# atmega.net
KiCad netlist of a schematic drawn in Altium Designer
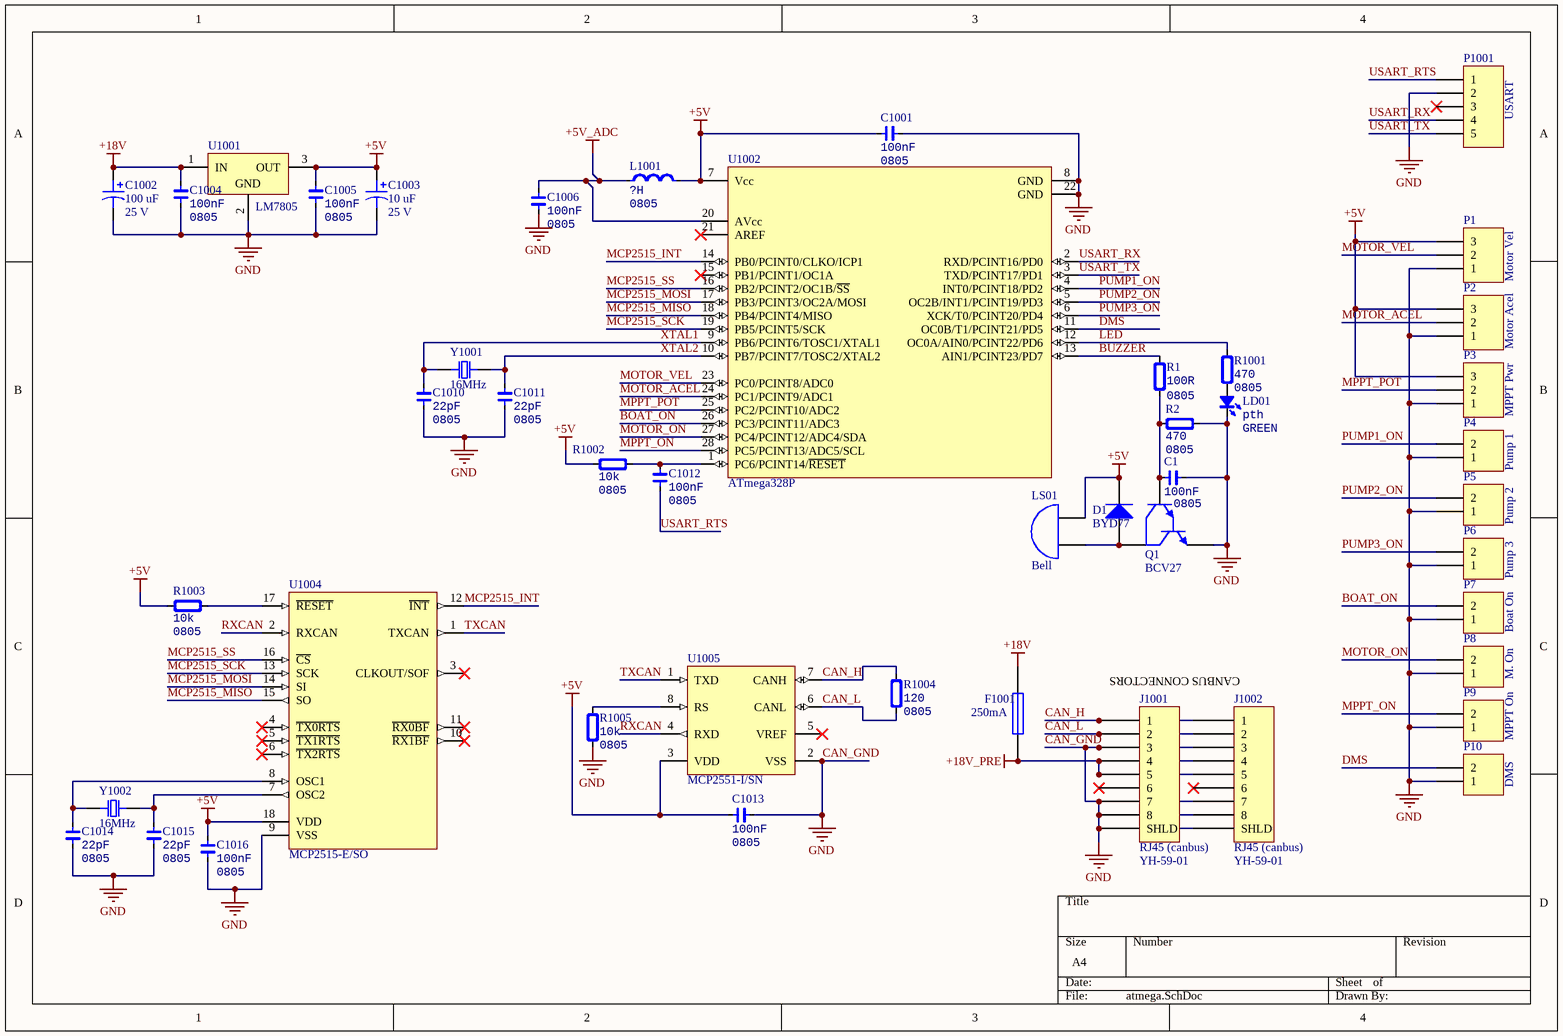
[diagram p0: atmega.SchDoc]

(export (version "E")
  (design (tool "Eeschema 10.0.6"))
  (components
    (comp (ref "C1")
      (value "100nF")
      (footprint "Zenite_Footprints:0805C")
      (description "Capacitor")
      (fields (field (name "TYPE") "0805"))
      (libsource (lib "") (part "Cap_0805_2"))
    )
    (comp (ref "C1001")
      (value "100nF")
      (footprint "Zenite_Footprints:0805C")
      (description "Capacitor")
      (fields (field (name "TYPE") "0805"))
      (libsource (lib "") (part "Cap_0805_2"))
    )
    (comp (ref "C1002")
      (value "100 uF")
      (footprint "CP3.5mm-8.0mm")
      (description "Solid Aluminum Capacitor with Organic Semiconductor Electrolyte: 100uF, 10V, Bulk Pack")
      (fields (field (name "VOLTAGE") "25 V") (field (name "Comment") "CapacitorPol"))
      (libsource (lib "R2R - Nova") (part "CapacitorPol"))
    )
    (comp (ref "C1003")
      (value "10 uF")
      (footprint "CP3.5mm-8.0mm")
      (description "Solid Aluminum Capacitor with Organic Semiconductor Electrolyte: 100uF, 10V, Bulk Pack")
      (fields (field (name "VOLTAGE") "25 V") (field (name "Comment") "CapacitorPol"))
      (libsource (lib "R2R - Nova") (part "CapacitorPol"))
    )
    (comp (ref "C1004")
      (value "100nF")
      (footprint "Zenite_Footprints:0805C")
      (description "Capacitor")
      (fields (field (name "TYPE") "0805"))
      (libsource (lib "SCH_Passive") (part "Cap_0805"))
    )
    (comp (ref "C1005")
      (value "100nF")
      (footprint "Zenite_Footprints:0805C")
      (description "Capacitor")
      (fields (field (name "TYPE") "0805"))
      (libsource (lib "SCH_Passive") (part "Cap_0805"))
    )
    (comp (ref "C1006")
      (value "100nF")
      (footprint "Zenite_Footprints:0805C")
      (description "Capacitor")
      (fields (field (name "TYPE") "0805"))
      (libsource (lib "SCH_Passive") (part "Cap_0805"))
    )
    (comp (ref "C1010")
      (value "22pF")
      (footprint "Zenite_Footprints:0805C")
      (description "Capacitor")
      (fields (field (name "TYPE") "0805"))
      (libsource (lib "SCH_Passive") (part "Cap_0805"))
    )
    (comp (ref "C1011")
      (value "22pF")
      (footprint "Zenite_Footprints:0805C")
      (description "Capacitor")
      (fields (field (name "TYPE") "0805"))
      (libsource (lib "SCH_Passive") (part "Cap_0805"))
    )
    (comp (ref "C1012")
      (value "100nF")
      (footprint "Zenite_Footprints:0805C")
      (description "Capacitor")
      (fields (field (name "TYPE") "0805"))
      (libsource (lib "") (part "Cap_0805_1"))
    )
    (comp (ref "C1013")
      (value "100nF")
      (footprint "Zenite_Footprints:0805C")
      (description "Capacitor")
      (fields (field (name "TYPE") "0805"))
      (libsource (lib "") (part "Cap_0805_2"))
    )
    (comp (ref "C1014")
      (value "22pF")
      (footprint "Zenite_Footprints:0805C")
      (description "Capacitor")
      (fields (field (name "TYPE") "0805"))
      (libsource (lib "SCH_Passive") (part "Cap_0805"))
    )
    (comp (ref "C1015")
      (value "22pF")
      (footprint "Zenite_Footprints:0805C")
      (description "Capacitor")
      (fields (field (name "TYPE") "0805"))
      (libsource (lib "SCH_Passive") (part "Cap_0805"))
    )
    (comp (ref "C1016")
      (value "100nF")
      (footprint "Zenite_Footprints:0805C")
      (description "Capacitor")
      (fields (field (name "TYPE") "0805"))
      (libsource (lib "") (part "Cap_0805_1"))
    )
    (comp (ref "D1")
      (value "BYD77")
      (footprint "DSO-C2/X2.3")
      (description "Default Diode")
      (libsource (lib "Miscellaneous Devices") (part "Diode"))
    )
    (comp (ref "F1001")
      (value "250mA")
      (footprint "Porta Fusivel")
      (description "Fuse")
      (libsource (lib "Miscellaneous Devices") (part "Fuse 1"))
    )
    (comp (ref "J1001")
      (value "RJ45 (canbus)")
      (footprint "ASSMANN A-2004-2-4-LP/FS")
      (description "YH-59-01")
      (fields (field (name "ALTIUM_VALUE") "YH-59-01"))
      (libsource (lib "Connectors") (part "Modular Jack with Shield"))
    )
    (comp (ref "J1002")
      (value "RJ45 (canbus)")
      (footprint "ASSMANN A-2004-2-4-LP/FS")
      (description "YH-59-01")
      (fields (field (name "ALTIUM_VALUE") "YH-59-01"))
      (libsource (lib "Connectors") (part "Modular Jack with Shield"))
    )
    (comp (ref "L1001")
      (value "?H")
      (footprint "Zenite_Footprints:0805L")
      (description "Inductor")
      (fields (field (name "TYPE") "0805"))
      (libsource (lib "SCH_Passive") (part "Ind_0805"))
    )
    (comp (ref "LD01")
      (value "GREEN")
      (footprint "LED3MM")
      (description "LED")
      (fields (field (name "TYPE") "pth"))
      (libsource (lib "SCH_Active") (part "LED_0805"))
    )
    (comp (ref "LS01")
      (value "Bell")
      (footprint "Buzzer5V")
      (description "Electrical Bell")
      (libsource (lib "Miscellaneous Devices") (part "Bell"))
    )
    (comp (ref "P1")
      (value "Motor Vel")
      (footprint "KRE_3")
      (description "Header, 3-Pin")
      (libsource (lib "Miscellaneous Connectors") (part "Header 3"))
    )
    (comp (ref "P2")
      (value "Motor Acel")
      (footprint "KRE_3")
      (description "Header, 3-Pin")
      (libsource (lib "Miscellaneous Connectors") (part "Header 3"))
    )
    (comp (ref "P3")
      (value "MPPT Pwr")
      (footprint "KRE_3")
      (description "Header, 3-Pin")
      (libsource (lib "Miscellaneous Connectors") (part "Header 3"))
    )
    (comp (ref "P4")
      (value "Pump 1")
      (footprint "KRE_2")
      (description "Terminal Block 1x2")
      (libsource (lib "R2R - Nova") (part "KRE_2"))
    )
    (comp (ref "P5")
      (value "Pump 2")
      (footprint "KRE_2")
      (description "Terminal Block 1x2")
      (libsource (lib "R2R - Nova") (part "KRE_2"))
    )
    (comp (ref "P6")
      (value "Pump 3")
      (footprint "KRE_2")
      (description "Terminal Block 1x2")
      (libsource (lib "R2R - Nova") (part "KRE_2"))
    )
    (comp (ref "P7")
      (value "Boat On")
      (footprint "KRE_2")
      (description "Terminal Block 1x2")
      (libsource (lib "R2R - Nova") (part "KRE_2"))
    )
    (comp (ref "P8")
      (value "M. On")
      (footprint "KRE_2")
      (description "Terminal Block 1x2")
      (libsource (lib "R2R - Nova") (part "KRE_2"))
    )
    (comp (ref "P9")
      (value "MPPT On")
      (footprint "KRE_2")
      (description "Terminal Block 1x2")
      (libsource (lib "R2R - Nova") (part "KRE_2"))
    )
    (comp (ref "P10")
      (value "DMS")
      (footprint "KRE_2")
      (description "Terminal Block 1x2")
      (libsource (lib "R2R - Nova") (part "KRE_2"))
    )
    (comp (ref "P1001")
      (value "USART")
      (footprint "Zenite_Footprints:HDR1X5")
      (description "Header, 5-Pin")
      (libsource (lib "R2R - Nova") (part "Header 5"))
    )
    (comp (ref "Q1")
      (value "BCV27")
      (footprint "SOT95P240-3N")
      (description "NPN Darlington Bipolar Transistor")
      (libsource (lib "Miscellaneous Devices") (part "NPN1"))
    )
    (comp (ref "R1")
      (value "100R")
      (footprint "Zenite_Footprints:0805R")
      (description "Resistor")
      (fields (field (name "TYPE") "0805"))
      (libsource (lib "SCH_Passive") (part "Res_0805"))
    )
    (comp (ref "R2")
      (value "470")
      (footprint "Zenite_Footprints:0805R")
      (description "Resistor")
      (fields (field (name "TYPE") "0805"))
      (libsource (lib "SCH_Passive") (part "Res_0805"))
    )
    (comp (ref "R1001")
      (value "470")
      (footprint "Zenite_Footprints:0805R")
      (description "Resistor")
      (fields (field (name "TYPE") "0805"))
      (libsource (lib "SCH_Passive") (part "Res_0805"))
    )
    (comp (ref "R1002")
      (value "10k")
      (footprint "Zenite_Footprints:0805R")
      (description "Resistor")
      (fields (field (name "TYPE") "0805"))
      (libsource (lib "SCH_Passive") (part "Res_0805"))
    )
    (comp (ref "R1003")
      (value "10k")
      (footprint "Zenite_Footprints:0805R")
      (description "Resistor")
      (fields (field (name "TYPE") "0805"))
      (libsource (lib "SCH_Passive") (part "Res_0805"))
    )
    (comp (ref "R1004")
      (value "120")
      (footprint "Zenite_Footprints:0805R")
      (description "Resistor")
      (fields (field (name "TYPE") "0805"))
      (libsource (lib "SCH_Passive") (part "Res_0805"))
    )
    (comp (ref "R1005")
      (value "10k")
      (footprint "Zenite_Footprints:0805R")
      (description "Resistor")
      (fields (field (name "TYPE") "0805"))
      (libsource (lib "SCH_Passive") (part "Res_0805"))
    )
    (comp (ref "U1001")
      (value "LM7805")
      (footprint "TO220_deitado")
      (description "Positive-Voltage Regulator")
      (libsource (lib "TI Power Mgt Voltage Regulator") (part "µA7805CKC"))
    )
    (comp (ref "U1002")
      (value "ATmega328P")
      (footprint "DIP28-300(100)")
      (libsource (lib "R2R - Nova") (part "ATmega328P"))
    )
    (comp (ref "U1004")
      (value "MCP2515-E/SO")
      (footprint "WSO18_L")
      (description "Stand-Alone CAN Controller With SPI Interface, 18-Pin SOIC, Extended Temperature")
      (libsource (lib "Altium Content Vault") (part "COM-CAN-MCP2515-18"))
    )
    (comp (ref "U1005")
      (value "MCP2551-I/SN")
      (footprint "SOIC08-150(50)")
      (libsource (lib "Altium Content Vault") (part "MCHP-MCP2551-SN8"))
    )
    (comp (ref "Y1001")
      (value "16MHz")
      (footprint "HC49-US-THT")
      (description "Crystal")
      (libsource (lib "R2R - Nova") (part "Crystal"))
    )
    (comp (ref "Y1002")
      (value "16MHz")
      (footprint "HC49-US-THT")
      (description "Crystal")
      (libsource (lib "R2R - Nova") (part "Crystal"))
    )
  )
  (nets
    (net (code "1") (name "+5V") (class "Default")
      (node (ref "C1001") (pin "1") (pinfunction "1_1") (pintype "passive"))
      (node (ref "C1003") (pin "1") (pinfunction "1_1") (pintype "passive"))
      (node (ref "C1005") (pin "2") (pinfunction "2_2") (pintype "passive"))
      (node (ref "C1013") (pin "1") (pinfunction "1_1") (pintype "passive"))
      (node (ref "C1016") (pin "1") (pinfunction "1_1") (pintype "passive"))
      (node (ref "D1") (pin "2") (pinfunction "K_2") (pintype "passive"))
      (node (ref "L1001") (pin "2") (pinfunction "2_2") (pintype "passive"))
      (node (ref "LS01") (pin "2") (pinfunction "B_2") (pintype "passive"))
      (node (ref "P1") (pin "3") (pinfunction "3_3") (pintype "passive"))
      (node (ref "P2") (pin "3") (pinfunction "3_3") (pintype "passive"))
      (node (ref "P3") (pin "3") (pinfunction "3_3") (pintype "passive"))
      (node (ref "R1002") (pin "1") (pinfunction "1_1") (pintype "passive"))
      (node (ref "R1003") (pin "1") (pinfunction "1_1") (pintype "passive"))
      (node (ref "U1001") (pin "3") (pinfunction "OUT_3") (pintype "power_in"))
      (node (ref "U1002") (pin "7") (pinfunction "Vcc_7") (pintype "passive"))
      (node (ref "U1004") (pin "18") (pinfunction "VDD_18") (pintype "power_in"))
      (node (ref "U1005") (pin "3") (pinfunction "VDD_3") (pintype "power_in"))
    )
    (net (code "2") (name "+5V_ADC") (class "Default")
      (node (ref "C1006") (pin "2") (pinfunction "2_2") (pintype "passive"))
      (node (ref "L1001") (pin "1") (pinfunction "1_1") (pintype "passive"))
      (node (ref "U1002") (pin "20") (pinfunction "AVcc_20") (pintype "passive"))
    )
    (net (code "3") (name "+18V") (class "Default")
      (node (ref "C1002") (pin "1") (pinfunction "1_1") (pintype "passive"))
      (node (ref "C1004") (pin "2") (pinfunction "2_2") (pintype "passive"))
      (node (ref "F1001") (pin "1") (pinfunction "1_1") (pintype "passive"))
      (node (ref "U1001") (pin "1") (pinfunction "IN_1") (pintype "power_in"))
    )
    (net (code "4") (name "+18V_PRE") (class "Default")
      (node (ref "F1001") (pin "2") (pinfunction "2_2") (pintype "passive"))
      (node (ref "J1001") (pin "4") (pinfunction "4_4") (pintype "passive"))
      (node (ref "J1001") (pin "5") (pinfunction "5_5") (pintype "passive"))
      (node (ref "J1002") (pin "4") (pinfunction "4_4") (pintype "passive"))
      (node (ref "J1002") (pin "5") (pinfunction "5_5") (pintype "passive"))
    )
    (net (code "5") (name "/BOAT_ON") (class "Default")
      (node (ref "P7") (pin "2") (pinfunction "2_2") (pintype "passive"))
      (node (ref "U1002") (pin "26") (pinfunction "PC3/PCINT11/ADC3_26") (pintype "bidirectional"))
    )
    (net (code "6") (name "/BUZZER") (class "Default")
      (node (ref "R1") (pin "1") (pinfunction "1_1") (pintype "passive"))
      (node (ref "U1002") (pin "13") (pinfunction "AIN1/PCINT23/PD7_13") (pintype "bidirectional"))
    )
    (net (code "7") (name "/CAN_H") (class "Default")
      (node (ref "J1001") (pin "1") (pinfunction "1_1") (pintype "passive"))
      (node (ref "J1002") (pin "1") (pinfunction "1_1") (pintype "passive"))
      (node (ref "R1004") (pin "2") (pinfunction "2_2") (pintype "passive"))
      (node (ref "U1005") (pin "7") (pinfunction "CANH_7") (pintype "bidirectional"))
    )
    (net (code "8") (name "/CAN_L") (class "Default")
      (node (ref "J1001") (pin "2") (pinfunction "2_2") (pintype "passive"))
      (node (ref "J1002") (pin "2") (pinfunction "2_2") (pintype "passive"))
      (node (ref "R1004") (pin "1") (pinfunction "1_1") (pintype "passive"))
      (node (ref "U1005") (pin "6") (pinfunction "CANL_6") (pintype "bidirectional"))
    )
    (net (code "9") (name "/DMS") (class "Default")
      (node (ref "P10") (pin "2") (pinfunction "2_2") (pintype "passive"))
      (node (ref "U1002") (pin "11") (pinfunction "OC0B/T1/PCINT21/PD5_11") (pintype "bidirectional"))
    )
    (net (code "10") (name "/LED") (class "Default")
      (node (ref "R1001") (pin "2") (pinfunction "2_2") (pintype "passive"))
      (node (ref "U1002") (pin "12") (pinfunction "OC0A/AIN0/PCINT22/PD6_12") (pintype "bidirectional"))
    )
    (net (code "11") (name "/MCP2515_INT") (class "Default")
      (node (ref "U1002") (pin "14") (pinfunction "PB0/PCINT0/CLKO/ICP1_14") (pintype "bidirectional"))
      (node (ref "U1004") (pin "12") (pinfunction "~{INT}_12") (pintype "output"))
    )
    (net (code "12") (name "/MCP2515_MISO") (class "Default")
      (node (ref "U1002") (pin "18") (pinfunction "PB4/PCINT4/MISO_18") (pintype "bidirectional"))
      (node (ref "U1004") (pin "15") (pinfunction "SO_15") (pintype "output"))
    )
    (net (code "13") (name "/MCP2515_MOSI") (class "Default")
      (node (ref "U1002") (pin "17") (pinfunction "PB3/PCINT3/OC2A/MOSI_17") (pintype "bidirectional"))
      (node (ref "U1004") (pin "14") (pinfunction "SI_14") (pintype "input"))
    )
    (net (code "14") (name "/MCP2515_SCK") (class "Default")
      (node (ref "U1002") (pin "19") (pinfunction "PB5/PCINT5/SCK_19") (pintype "bidirectional"))
      (node (ref "U1004") (pin "13") (pinfunction "SCK_13") (pintype "input"))
    )
    (net (code "15") (name "/MCP2515_SS") (class "Default")
      (node (ref "U1002") (pin "16") (pinfunction "PB2/PCINT2/OC1B/~{SS}_16") (pintype "bidirectional"))
      (node (ref "U1004") (pin "16") (pinfunction "~{CS}_16") (pintype "input"))
    )
    (net (code "16") (name "/MOTOR_ACEL") (class "Default")
      (node (ref "P2") (pin "2") (pinfunction "2_2") (pintype "passive"))
      (node (ref "U1002") (pin "24") (pinfunction "PC1/PCINT9/ADC1_24") (pintype "bidirectional"))
    )
    (net (code "17") (name "/MOTOR_ON") (class "Default")
      (node (ref "P8") (pin "2") (pinfunction "2_2") (pintype "passive"))
      (node (ref "U1002") (pin "27") (pinfunction "PC4/PCINT12/ADC4/SDA_27") (pintype "bidirectional"))
    )
    (net (code "18") (name "/MOTOR_VEL") (class "Default")
      (node (ref "P1") (pin "2") (pinfunction "2_2") (pintype "passive"))
      (node (ref "U1002") (pin "23") (pinfunction "PC0/PCINT8/ADC0_23") (pintype "bidirectional"))
    )
    (net (code "19") (name "/MPPT_ON") (class "Default")
      (node (ref "P9") (pin "2") (pinfunction "2_2") (pintype "passive"))
      (node (ref "U1002") (pin "28") (pinfunction "PC5/PCINT13/ADC5/SCL_28") (pintype "bidirectional"))
    )
    (net (code "20") (name "/MPPT_POT") (class "Default")
      (node (ref "P3") (pin "2") (pinfunction "2_2") (pintype "passive"))
      (node (ref "U1002") (pin "25") (pinfunction "PC2/PCINT10/ADC2_25") (pintype "bidirectional"))
    )
    (net (code "21") (name "/PUMP1_ON") (class "Default")
      (node (ref "P4") (pin "2") (pinfunction "2_2") (pintype "passive"))
      (node (ref "U1002") (pin "4") (pinfunction "INT0/PCINT18/PD2_4") (pintype "bidirectional"))
    )
    (net (code "22") (name "/PUMP2_ON") (class "Default")
      (node (ref "P5") (pin "2") (pinfunction "2_2") (pintype "passive"))
      (node (ref "U1002") (pin "5") (pinfunction "OC2B/INT1/PCINT19/PD3_5") (pintype "bidirectional"))
    )
    (net (code "23") (name "/PUMP3_ON") (class "Default")
      (node (ref "P6") (pin "2") (pinfunction "2_2") (pintype "passive"))
      (node (ref "U1002") (pin "6") (pinfunction "XCK/T0/PCINT20/PD4_6") (pintype "bidirectional"))
    )
    (net (code "24") (name "/RXCAN") (class "Default")
      (node (ref "U1004") (pin "2") (pinfunction "RXCAN_2") (pintype "input"))
      (node (ref "U1005") (pin "4") (pinfunction "RXD_4") (pintype "output"))
    )
    (net (code "25") (name "/TXCAN") (class "Default")
      (node (ref "U1004") (pin "1") (pinfunction "TXCAN_1") (pintype "output"))
      (node (ref "U1005") (pin "1") (pinfunction "TXD_1") (pintype "input"))
    )
    (net (code "26") (name "/USART_RTS") (class "Default")
      (node (ref "C1012") (pin "2") (pinfunction "2_2") (pintype "passive"))
      (node (ref "P1001") (pin "1") (pinfunction "1_1") (pintype "passive"))
    )
    (net (code "27") (name "/USART_RX") (class "Default")
      (node (ref "P1001") (pin "4") (pinfunction "4_4") (pintype "passive"))
      (node (ref "U1002") (pin "2") (pinfunction "RXD/PCINT16/PD0_2") (pintype "bidirectional"))
    )
    (net (code "28") (name "/USART_TX") (class "Default")
      (node (ref "P1001") (pin "5") (pinfunction "5_5") (pintype "passive"))
      (node (ref "U1002") (pin "3") (pinfunction "TXD/PCINT17/PD1_3") (pintype "bidirectional"))
    )
    (net (code "29") (name "/XTAL1") (class "Default")
      (node (ref "C1010") (pin "2") (pinfunction "2_2") (pintype "passive"))
      (node (ref "U1002") (pin "9") (pinfunction "PB6/PCINT6/TOSC1/XTAL1_9") (pintype "bidirectional"))
      (node (ref "Y1001") (pin "1") (pinfunction "1_1") (pintype "passive"))
    )
    (net (code "30") (name "/XTAL2") (class "Default")
      (node (ref "C1011") (pin "2") (pinfunction "2_2") (pintype "passive"))
      (node (ref "U1002") (pin "10") (pinfunction "PB7/PCINT7/TOSC2/XTAL2_10") (pintype "bidirectional"))
      (node (ref "Y1001") (pin "2") (pinfunction "2_2") (pintype "passive"))
    )
    (net (code "31") (name "GND") (class "Default")
      (node (ref "C1") (pin "2") (pinfunction "2_2") (pintype "passive"))
      (node (ref "C1001") (pin "2") (pinfunction "2_2") (pintype "passive"))
      (node (ref "C1002") (pin "2") (pinfunction "2_2") (pintype "passive"))
      (node (ref "C1003") (pin "2") (pinfunction "2_2") (pintype "passive"))
      (node (ref "C1004") (pin "1") (pinfunction "1_1") (pintype "passive"))
      (node (ref "C1005") (pin "1") (pinfunction "1_1") (pintype "passive"))
      (node (ref "C1006") (pin "1") (pinfunction "1_1") (pintype "passive"))
      (node (ref "C1010") (pin "1") (pinfunction "1_1") (pintype "passive"))
      (node (ref "C1011") (pin "1") (pinfunction "1_1") (pintype "passive"))
      (node (ref "C1013") (pin "2") (pinfunction "2_2") (pintype "passive"))
      (node (ref "C1014") (pin "1") (pinfunction "1_1") (pintype "passive"))
      (node (ref "C1015") (pin "1") (pinfunction "1_1") (pintype "passive"))
      (node (ref "C1016") (pin "2") (pinfunction "2_2") (pintype "passive"))
      (node (ref "J1001") (pin "3") (pinfunction "3_3") (pintype "passive"))
      (node (ref "J1001") (pin "7") (pinfunction "7_7") (pintype "passive"))
      (node (ref "J1001") (pin "8") (pinfunction "8_8") (pintype "passive"))
      (node (ref "J1001") (pin "S") (pinfunction "SHLD_S") (pintype "passive"))
      (node (ref "J1002") (pin "3") (pinfunction "3_3") (pintype "passive"))
      (node (ref "J1002") (pin "7") (pinfunction "7_7") (pintype "passive"))
      (node (ref "J1002") (pin "8") (pinfunction "8_8") (pintype "passive"))
      (node (ref "J1002") (pin "S") (pinfunction "SHLD_S") (pintype "passive"))
      (node (ref "LD01") (pin "2") (pinfunction "K_2") (pintype "passive"))
      (node (ref "P1") (pin "1") (pinfunction "1_1") (pintype "passive"))
      (node (ref "P10") (pin "1") (pinfunction "1_1") (pintype "passive"))
      (node (ref "P1001") (pin "2") (pinfunction "2_2") (pintype "passive"))
      (node (ref "P2") (pin "1") (pinfunction "1_1") (pintype "passive"))
      (node (ref "P3") (pin "1") (pinfunction "1_1") (pintype "passive"))
      (node (ref "P4") (pin "1") (pinfunction "1_1") (pintype "passive"))
      (node (ref "P5") (pin "1") (pinfunction "1_1") (pintype "passive"))
      (node (ref "P6") (pin "1") (pinfunction "1_1") (pintype "passive"))
      (node (ref "P7") (pin "1") (pinfunction "1_1") (pintype "passive"))
      (node (ref "P8") (pin "1") (pinfunction "1_1") (pintype "passive"))
      (node (ref "P9") (pin "1") (pinfunction "1_1") (pintype "passive"))
      (node (ref "Q1") (pin "3") (pinfunction "E_3") (pintype "passive"))
      (node (ref "R1005") (pin "2") (pinfunction "2_2") (pintype "passive"))
      (node (ref "R2") (pin "1") (pinfunction "1_1") (pintype "passive"))
      (node (ref "U1001") (pin "2") (pinfunction "GND_2") (pintype "power_in"))
      (node (ref "U1002") (pin "22") (pinfunction "GND_22") (pintype "passive"))
      (node (ref "U1002") (pin "8") (pinfunction "GND_8") (pintype "passive"))
      (node (ref "U1004") (pin "9") (pinfunction "VSS_9") (pintype "power_in"))
      (node (ref "U1005") (pin "2") (pinfunction "VSS_2") (pintype "power_in"))
    )
    (net (code "32") (name "Net-(D1-A)") (class "Default")
      (node (ref "D1") (pin "1") (pinfunction "A_1") (pintype "passive"))
      (node (ref "LS01") (pin "1") (pinfunction "A_1") (pintype "passive"))
      (node (ref "Q1") (pin "1") (pinfunction "C_1") (pintype "passive"))
    )
    (net (code "33") (name "Net-(LD01-A)") (class "Default")
      (node (ref "LD01") (pin "1") (pinfunction "A_1") (pintype "passive"))
      (node (ref "R1001") (pin "1") (pinfunction "1_1") (pintype "passive"))
    )
    (net (code "34") (name "Net-(Q1-B)") (class "Default")
      (node (ref "C1") (pin "1") (pinfunction "1_1") (pintype "passive"))
      (node (ref "Q1") (pin "2") (pinfunction "B_2") (pintype "passive"))
      (node (ref "R1") (pin "2") (pinfunction "2_2") (pintype "passive"))
      (node (ref "R2") (pin "2") (pinfunction "2_2") (pintype "passive"))
    )
    (net (code "35") (name "Net-(U1002-PC6{slash}PCINT14{slash}~{RESET})") (class "Default")
      (node (ref "C1012") (pin "1") (pinfunction "1_1") (pintype "passive"))
      (node (ref "R1002") (pin "2") (pinfunction "2_2") (pintype "passive"))
      (node (ref "U1002") (pin "1") (pinfunction "PC6/PCINT14/~{RESET}_1") (pintype "bidirectional"))
    )
    (net (code "36") (name "Net-(U1004-OSC1)") (class "Default")
      (node (ref "C1014") (pin "2") (pinfunction "2_2") (pintype "passive"))
      (node (ref "U1004") (pin "8") (pinfunction "OSC1_8") (pintype "input"))
      (node (ref "Y1002") (pin "1") (pinfunction "1_1") (pintype "passive"))
    )
    (net (code "37") (name "Net-(U1004-OSC2)") (class "Default")
      (node (ref "C1015") (pin "2") (pinfunction "2_2") (pintype "passive"))
      (node (ref "U1004") (pin "7") (pinfunction "OSC2_7") (pintype "output"))
      (node (ref "Y1002") (pin "2") (pinfunction "2_2") (pintype "passive"))
    )
    (net (code "38") (name "Net-(U1004-~{RESET})") (class "Default")
      (node (ref "R1003") (pin "2") (pinfunction "2_2") (pintype "passive"))
      (node (ref "U1004") (pin "17") (pinfunction "~{RESET}_17") (pintype "input"))
    )
    (net (code "39") (name "Net-(U1005-RS)") (class "Default")
      (node (ref "R1005") (pin "1") (pinfunction "1_1") (pintype "passive"))
      (node (ref "U1005") (pin "8") (pinfunction "RS_8") (pintype "input"))
    )
    (net (code "40") (name "unconnected-(J1001-Pad6)") (class "Default")
      (node (ref "J1001") (pin "6") (pinfunction "6_6") (pintype "passive+no_connect"))
    )
    (net (code "41") (name "unconnected-(J1002-Pad6)") (class "Default")
      (node (ref "J1002") (pin "6") (pinfunction "6_6") (pintype "passive+no_connect"))
    )
    (net (code "42") (name "unconnected-(P1001-Pad3)") (class "Default")
      (node (ref "P1001") (pin "3") (pinfunction "3_3") (pintype "passive+no_connect"))
    )
    (net (code "43") (name "unconnected-(U1002-AREF-Pad21)") (class "Default")
      (node (ref "U1002") (pin "21") (pinfunction "AREF_21") (pintype "passive+no_connect"))
    )
    (net (code "44") (name "unconnected-(U1002-PB1{slash}PCINT1{slash}OC1A-Pad15)") (class "Default")
      (node (ref "U1002") (pin "15") (pinfunction "PB1/PCINT1/OC1A_15") (pintype "bidirectional+no_connect"))
    )
    (net (code "45") (name "unconnected-(U1004-CLKOUT{slash}SOF-Pad3)") (class "Default")
      (node (ref "U1004") (pin "3") (pinfunction "CLKOUT/SOF_3") (pintype "output+no_connect"))
    )
    (net (code "46") (name "unconnected-(U1004-~{RX0BF}-Pad11)") (class "Default")
      (node (ref "U1004") (pin "11") (pinfunction "~{RX0BF}_11") (pintype "output+no_connect"))
    )
    (net (code "47") (name "unconnected-(U1004-~{RX1BF}-Pad10)") (class "Default")
      (node (ref "U1004") (pin "10") (pinfunction "~{RX1BF}_10") (pintype "output+no_connect"))
    )
    (net (code "48") (name "unconnected-(U1004-~{TX0RTS}-Pad4)") (class "Default")
      (node (ref "U1004") (pin "4") (pinfunction "~{TX0RTS}_4") (pintype "input+no_connect"))
    )
    (net (code "49") (name "unconnected-(U1004-~{TX1RTS}-Pad5)") (class "Default")
      (node (ref "U1004") (pin "5") (pinfunction "~{TX1RTS}_5") (pintype "input+no_connect"))
    )
    (net (code "50") (name "unconnected-(U1004-~{TX2RTS}-Pad6)") (class "Default")
      (node (ref "U1004") (pin "6") (pinfunction "~{TX2RTS}_6") (pintype "input+no_connect"))
    )
    (net (code "51") (name "unconnected-(U1005-VREF-Pad5)") (class "Default")
      (node (ref "U1005") (pin "5") (pinfunction "VREF_5") (pintype "power_in+no_connect"))
    )
  )
)
